# lcd-screen.net
KiCad netlist of a schematic drawn in EAGLE
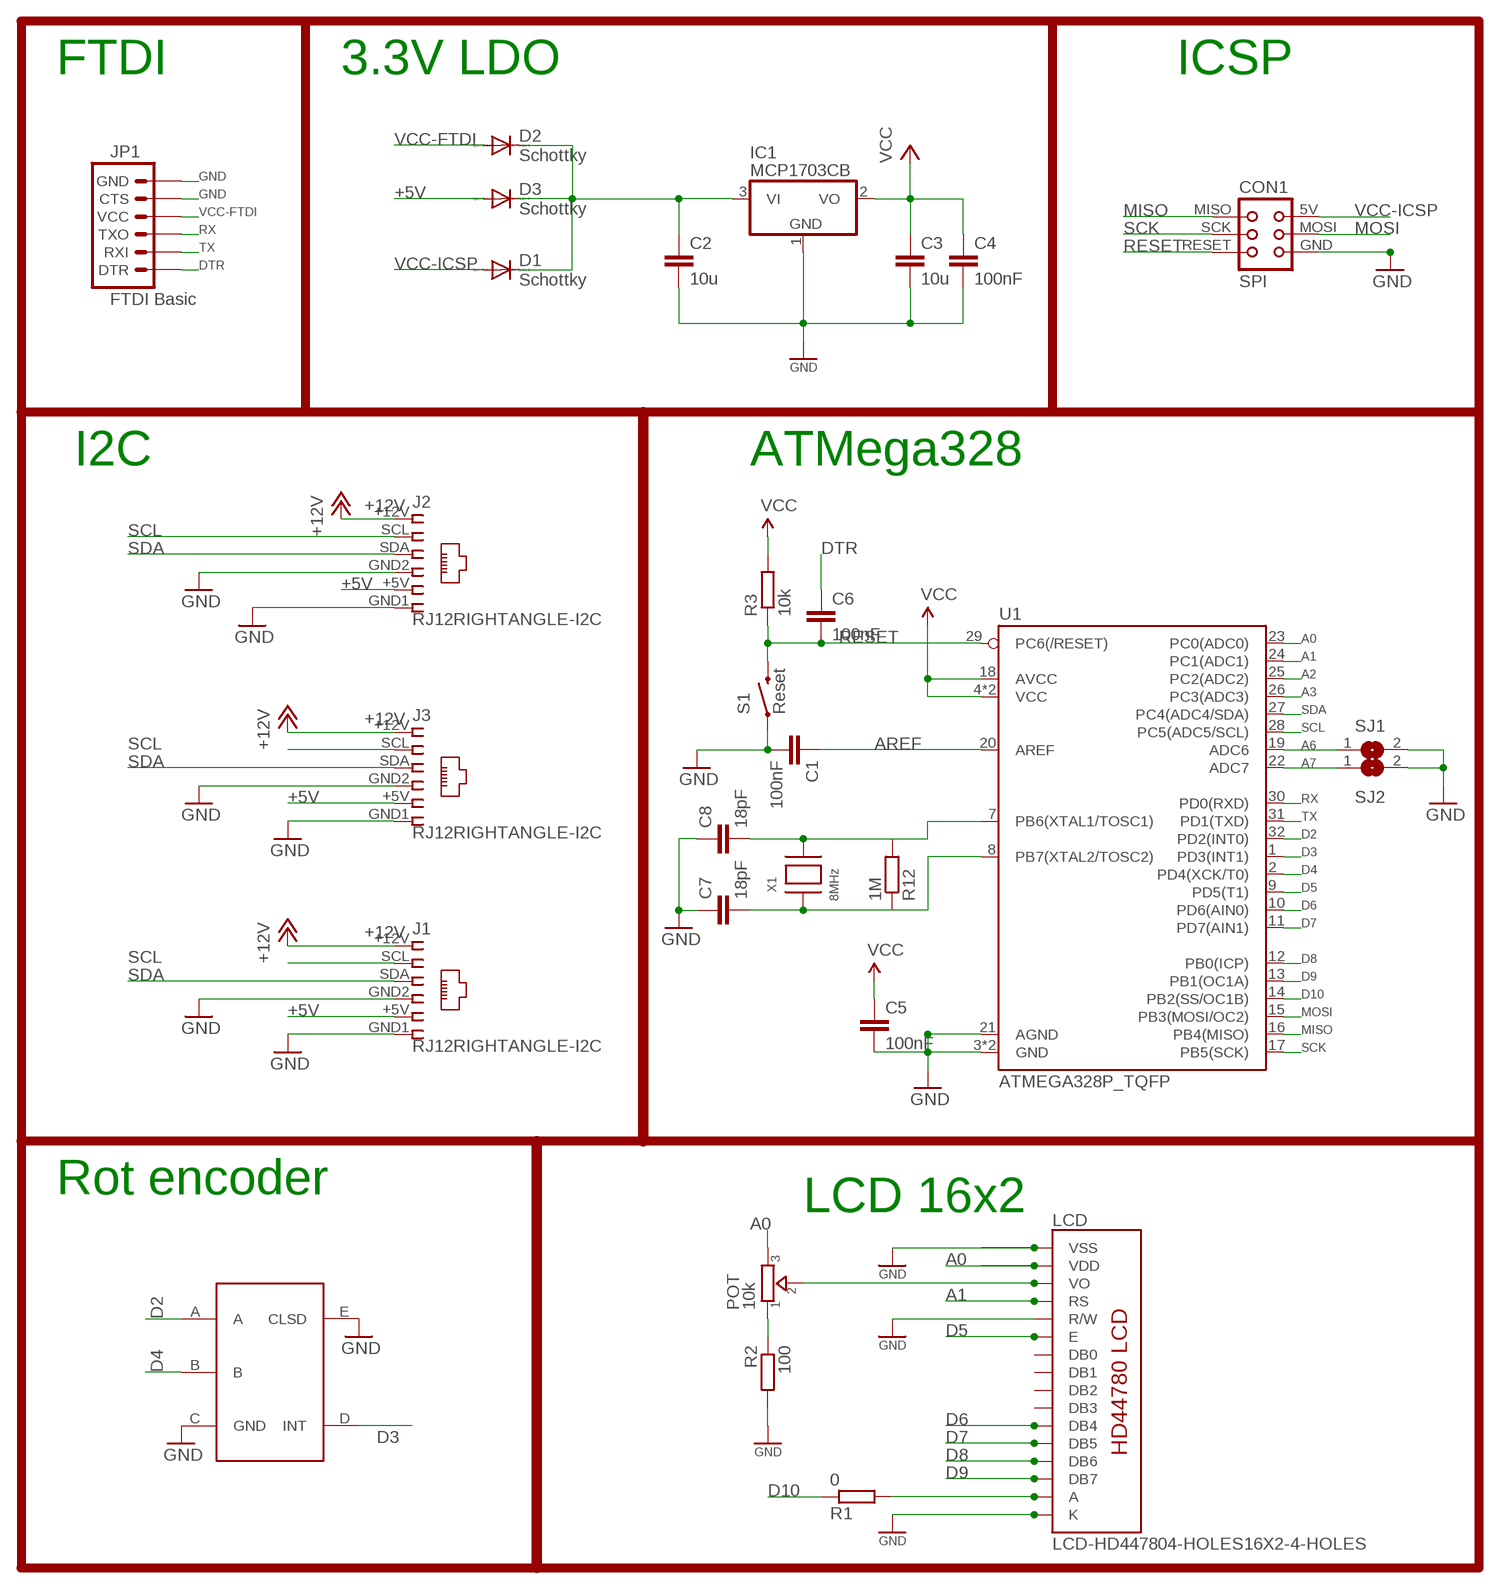
[diagram p0: schematic, sheet 1]

(export (version "E")
  (design (tool "Eeschema 10.0.6"))
  (components
    (comp (ref "C1")
      (value "100nF")
      (footprint "eagle-import:C0805K")
      (fields (field (name "MPN") "80-C1206C104K5R"))
      (libsource (lib "eagle-import") (part "C-EUC0805K"))
    )
    (comp (ref "C2")
      (value "10u")
      (footprint "eagle-import:C0805K")
      (fields (field (name "MPN") "77-VJ1206V106ZXQTBC"))
      (libsource (lib "eagle-import") (part "C-EUC0805K"))
    )
    (comp (ref "C3")
      (value "10u")
      (footprint "eagle-import:C0805K")
      (fields (field (name "MPN") "77-VJ1206V106ZXQTBC"))
      (libsource (lib "eagle-import") (part "C-EUC0805K"))
    )
    (comp (ref "C4")
      (value "100nF")
      (footprint "eagle-import:C0805K")
      (fields (field (name "MPN") "80-C1206C104K5R"))
      (libsource (lib "eagle-import") (part "C-EUC0805K"))
    )
    (comp (ref "C5")
      (value "100nF")
      (footprint "eagle-import:C0805K")
      (fields (field (name "MPN") "80-C1206C104K5R"))
      (libsource (lib "eagle-import") (part "C-EUC0805K"))
    )
    (comp (ref "C6")
      (value "100nF")
      (footprint "eagle-import:C0805K")
      (fields (field (name "MPN") "80-C1206C104K5R"))
      (libsource (lib "eagle-import") (part "C-EUC0805K"))
    )
    (comp (ref "C7")
      (value "18pF")
      (footprint "eagle-import:C0805K")
      (fields (field (name "MPN") "77-VJ1206A180JXXPBC"))
      (libsource (lib "eagle-import") (part "C-EUC0805K"))
    )
    (comp (ref "C8")
      (value "18pF")
      (footprint "eagle-import:C0805K")
      (fields (field (name "MPN") "77-VJ1206A180JXXPBC"))
      (libsource (lib "eagle-import") (part "C-EUC0805K"))
    )
    (comp (ref "CON1")
      (value "SPI")
      (footprint "eagle-import:TC2030-MCP")
      (libsource (lib "eagle-import") (part "TINYISPTAG"))
    )
    (comp (ref "D1")
      (value "Schottky")
      (footprint "eagle-import:SOD123")
      (fields (field (name "MPN") "621-1N5819HW-F"))
      (libsource (lib "eagle-import") (part "MBR0520LT"))
    )
    (comp (ref "D2")
      (value "Schottky")
      (footprint "eagle-import:SOD123")
      (fields (field (name "MPN") "621-1N5819HW-F"))
      (libsource (lib "eagle-import") (part "MBR0520LT"))
    )
    (comp (ref "D3")
      (value "Schottky")
      (footprint "eagle-import:SOD123")
      (fields (field (name "MPN") "621-1N5819HW-F"))
      (libsource (lib "eagle-import") (part "MBR0520LT"))
    )
    (comp (ref "IC1")
      (value "MCP1703CB")
      (footprint "eagle-import:SOT23")
      (libsource (lib "eagle-import") (part "MCP1703CB"))
    )
    (comp (ref "J1")
      (value "RJ12RIGHTANGLE-I2C")
      (footprint "eagle-import:RJ12-RIGHTANGLE-I2C")
      (libsource (lib "eagle-import") (part "RJ12RIGHTANGLE-I2C"))
    )
    (comp (ref "J2")
      (value "RJ12RIGHTANGLE-I2C")
      (footprint "eagle-import:RJ12-RIGHTANGLE-I2C")
      (libsource (lib "eagle-import") (part "RJ12RIGHTANGLE-I2C"))
    )
    (comp (ref "J3")
      (value "RJ12RIGHTANGLE-I2C")
      (footprint "eagle-import:RJ12-RIGHTANGLE-I2C")
      (libsource (lib "eagle-import") (part "RJ12RIGHTANGLE-I2C"))
    )
    (comp (ref "JP1")
      (value "FTDI Basic")
      (footprint "eagle-import:1X06")
      (libsource (lib "eagle-import") (part "ARDUINO_SERIAL_PROGRAMPTH"))
    )
    (comp (ref "LCD")
      (value "LCD-HD447804-HOLES16X2-4-HOLES")
      (footprint "eagle-import:LCD-16X2-4HOLES")
      (libsource (lib "eagle-import") (part "LCD-HD4478016X2-4-HOLES4-HOLES"))
    )
    (comp (ref "POT")
      (value "10k")
      (footprint "eagle-import:TRIMMER_3362P")
      (libsource (lib "eagle-import") (part "TRIMMER-3362P"))
    )
    (comp (ref "R1")
      (value "0")
      (footprint "eagle-import:R0805")
      (libsource (lib "eagle-import") (part "rcl_334_R-EU_R0805"))
    )
    (comp (ref "R2")
      (value "100")
      (footprint "eagle-import:R0805")
      (libsource (lib "eagle-import") (part "R-EU_R0805"))
    )
    (comp (ref "R3")
      (value "10k")
      (footprint "eagle-import:R0805")
      (libsource (lib "eagle-import") (part "R-EU_R0805"))
    )
    (comp (ref "R12")
      (value "1M")
      (footprint "eagle-import:R0805")
      (libsource (lib "eagle-import") (part "R-EU_R0805"))
    )
    (comp (ref "S1")
      (value "Reset")
      (footprint "eagle-import:TACTILE-SWITCH-SMD-ALT01")
      (libsource (lib "eagle-import") (part "SWITCH-MOMENTARY-2SMD-ALT01"))
    )
    (comp (ref "SJ1") (value "SJ") (footprint "eagle-import:SJ") (libsource (lib "eagle-import") (part "SJ")))
    (comp (ref "SJ2") (value "SJ") (footprint "eagle-import:SJ") (libsource (lib "eagle-import") (part "SJ")))
    (comp (ref "U$1")
      (value "EC11E")
      (footprint "eagle-import:EC11E")
      (libsource (lib "eagle-import") (part "EC11E"))
    )
    (comp (ref "U1")
      (value "ATMEGA328P_TQFP")
      (footprint "eagle-import:TQFP32-08")
      (libsource (lib "eagle-import") (part "ATMEGA328P_TQFP"))
    )
    (comp (ref "X1")
      (value "8MHz")
      (footprint "eagle-import:NX6035")
      (fields (field (name "MPN") "729-F60800010"))
      (libsource (lib "eagle-import") (part "XTALNX6035"))
    )
  )
  (nets
    (net (code "1") (name "+12V") (class "Default")
      (node (ref "J1") (pin "+12V") (pinfunction "1_+12V") (pintype "bidirectional"))
      (node (ref "J2") (pin "+12V") (pinfunction "1_+12V") (pintype "bidirectional"))
      (node (ref "J3") (pin "+12V") (pinfunction "1_+12V") (pintype "bidirectional"))
    )
    (net (code "2") (name "/+5V") (class "Default")
      (node (ref "D3") (pin "A") (pinfunction "A_A") (pintype "passive"))
      (node (ref "J1") (pin "+5V") (pinfunction "5_+5V") (pintype "bidirectional"))
      (node (ref "J2") (pin "+5V") (pinfunction "5_+5V") (pintype "bidirectional"))
      (node (ref "J3") (pin "+5V") (pinfunction "5_+5V") (pintype "bidirectional"))
    )
    (net (code "3") (name "/A0") (class "Default")
      (node (ref "LCD") (pin "2") (pinfunction "VDD_2") (pintype "power_in"))
      (node (ref "POT") (pin "3") (pinfunction "3_3") (pintype "passive"))
      (node (ref "U1") (pin "23") (pinfunction "PC0(ADC0)_23") (pintype "bidirectional"))
    )
    (net (code "4") (name "/A1") (class "Default")
      (node (ref "LCD") (pin "4") (pinfunction "RS_4") (pintype "input"))
      (node (ref "U1") (pin "24") (pinfunction "PC1(ADC1)_24") (pintype "bidirectional"))
    )
    (net (code "5") (name "/A2") (class "Default")
      (node (ref "U1") (pin "25") (pinfunction "PC2(ADC2)_25") (pintype "bidirectional"))
    )
    (net (code "6") (name "/A3") (class "Default")
      (node (ref "U1") (pin "26") (pinfunction "PC3(ADC3)_26") (pintype "bidirectional"))
    )
    (net (code "7") (name "/A6") (class "Default")
      (node (ref "SJ1") (pin "1") (pinfunction "1_1") (pintype "passive"))
      (node (ref "U1") (pin "19") (pinfunction "ADC6_19") (pintype "bidirectional"))
    )
    (net (code "8") (name "/A7") (class "Default")
      (node (ref "SJ2") (pin "1") (pinfunction "1_1") (pintype "passive"))
      (node (ref "U1") (pin "22") (pinfunction "ADC7_22") (pintype "bidirectional"))
    )
    (net (code "9") (name "/AREF") (class "Default")
      (node (ref "C1") (pin "1") (pinfunction "1_1") (pintype "passive"))
      (node (ref "U1") (pin "20") (pinfunction "AREF_20") (pintype "bidirectional"))
    )
    (net (code "10") (name "/D2") (class "Default")
      (node (ref "U$1") (pin "A") (pinfunction "A_A") (pintype "bidirectional"))
      (node (ref "U1") (pin "32") (pinfunction "PD2(INT0)_32") (pintype "bidirectional"))
    )
    (net (code "11") (name "/D3") (class "Default")
      (node (ref "U$1") (pin "D") (pinfunction "INT_D") (pintype "bidirectional"))
      (node (ref "U1") (pin "1") (pinfunction "PD3(INT1)_1") (pintype "bidirectional"))
    )
    (net (code "12") (name "/D4") (class "Default")
      (node (ref "U$1") (pin "B") (pinfunction "B_B") (pintype "bidirectional"))
      (node (ref "U1") (pin "2") (pinfunction "PD4(XCK/T0)_2") (pintype "bidirectional"))
    )
    (net (code "13") (name "/D5") (class "Default")
      (node (ref "LCD") (pin "6") (pinfunction "E_6") (pintype "input"))
      (node (ref "U1") (pin "9") (pinfunction "PD5(T1)_9") (pintype "bidirectional"))
    )
    (net (code "14") (name "/D6") (class "Default")
      (node (ref "LCD") (pin "11") (pinfunction "DB4_11") (pintype "bidirectional"))
      (node (ref "U1") (pin "10") (pinfunction "PD6(AIN0)_10") (pintype "bidirectional"))
    )
    (net (code "15") (name "/D7") (class "Default")
      (node (ref "LCD") (pin "12") (pinfunction "DB5_12") (pintype "bidirectional"))
      (node (ref "U1") (pin "11") (pinfunction "PD7(AIN1)_11") (pintype "bidirectional"))
    )
    (net (code "16") (name "/D8") (class "Default")
      (node (ref "LCD") (pin "13") (pinfunction "DB6_13") (pintype "bidirectional"))
      (node (ref "U1") (pin "12") (pinfunction "PB0(ICP)_12") (pintype "bidirectional"))
    )
    (net (code "17") (name "/D9") (class "Default")
      (node (ref "LCD") (pin "14") (pinfunction "DB7_14") (pintype "bidirectional"))
      (node (ref "U1") (pin "13") (pinfunction "PB1(OC1A)_13") (pintype "bidirectional"))
    )
    (net (code "18") (name "/D10") (class "Default")
      (node (ref "R1") (pin "1") (pinfunction "1_1") (pintype "passive"))
      (node (ref "U1") (pin "14") (pinfunction "PB2(SS/OC1B)_14") (pintype "bidirectional"))
    )
    (net (code "19") (name "/DTR") (class "Default")
      (node (ref "C6") (pin "1") (pinfunction "1_1") (pintype "passive"))
      (node (ref "JP1") (pin "1") (pinfunction "DTR_1") (pintype "passive"))
    )
    (net (code "20") (name "/MISO") (class "Default")
      (node (ref "CON1") (pin "MISO") (pinfunction "MISO_MISO") (pintype "passive"))
      (node (ref "U1") (pin "16") (pinfunction "PB4(MISO)_16") (pintype "bidirectional"))
    )
    (net (code "21") (name "/MOSI") (class "Default")
      (node (ref "CON1") (pin "MOSI") (pinfunction "MOSI_MOSI") (pintype "passive"))
      (node (ref "U1") (pin "15") (pinfunction "PB3(MOSI/OC2)_15") (pintype "bidirectional"))
    )
    (net (code "22") (name "/RESET") (class "Default")
      (node (ref "C6") (pin "2") (pinfunction "2_2") (pintype "passive"))
      (node (ref "CON1") (pin "RESET") (pinfunction "RESET_RESET") (pintype "passive"))
      (node (ref "R3") (pin "1") (pinfunction "1_1") (pintype "passive"))
      (node (ref "S1") (pin "3") (pinfunction "2_3") (pintype "passive"))
      (node (ref "S1") (pin "4") (pinfunction "2_4") (pintype "passive"))
      (node (ref "U1") (pin "29") (pinfunction "PC6(/RESET)_29") (pintype "bidirectional"))
    )
    (net (code "23") (name "/RX") (class "Default")
      (node (ref "JP1") (pin "3") (pinfunction "TXO_3") (pintype "passive"))
      (node (ref "U1") (pin "30") (pinfunction "PD0(RXD)_30") (pintype "bidirectional"))
    )
    (net (code "24") (name "/SCK") (class "Default")
      (node (ref "CON1") (pin "SCK") (pinfunction "SCK_SCK") (pintype "passive"))
      (node (ref "U1") (pin "17") (pinfunction "PB5(SCK)_17") (pintype "bidirectional"))
    )
    (net (code "25") (name "/SCL") (class "Default")
      (node (ref "J1") (pin "SCL") (pinfunction "2_SCL") (pintype "bidirectional"))
      (node (ref "J2") (pin "SCL") (pinfunction "2_SCL") (pintype "bidirectional"))
      (node (ref "J3") (pin "SCL") (pinfunction "2_SCL") (pintype "bidirectional"))
      (node (ref "U1") (pin "28") (pinfunction "PC5(ADC5/SCL)_28") (pintype "bidirectional"))
    )
    (net (code "26") (name "/SDA") (class "Default")
      (node (ref "J1") (pin "SDA") (pinfunction "3_SDA") (pintype "bidirectional"))
      (node (ref "J2") (pin "SDA") (pinfunction "3_SDA") (pintype "bidirectional"))
      (node (ref "J3") (pin "SDA") (pinfunction "3_SDA") (pintype "bidirectional"))
      (node (ref "U1") (pin "27") (pinfunction "PC4(ADC4/SDA)_27") (pintype "bidirectional"))
    )
    (net (code "27") (name "/TX") (class "Default")
      (node (ref "JP1") (pin "2") (pinfunction "RXI_2") (pintype "passive"))
      (node (ref "U1") (pin "31") (pinfunction "PD1(TXD)_31") (pintype "bidirectional"))
    )
    (net (code "28") (name "/VCC-FTDI") (class "Default")
      (node (ref "D2") (pin "A") (pinfunction "A_A") (pintype "passive"))
      (node (ref "JP1") (pin "4") (pinfunction "VCC_4") (pintype "passive"))
    )
    (net (code "29") (name "/VCC-ICSP") (class "Default")
      (node (ref "CON1") (pin "5V") (pinfunction "VCC_5V") (pintype "passive"))
      (node (ref "D1") (pin "A") (pinfunction "A_A") (pintype "passive"))
    )
    (net (code "30") (name "GND") (class "Default")
      (node (ref "C1") (pin "2") (pinfunction "2_2") (pintype "passive"))
      (node (ref "C2") (pin "2") (pinfunction "2_2") (pintype "passive"))
      (node (ref "C3") (pin "2") (pinfunction "2_2") (pintype "passive"))
      (node (ref "C4") (pin "2") (pinfunction "2_2") (pintype "passive"))
      (node (ref "C5") (pin "2") (pinfunction "2_2") (pintype "passive"))
      (node (ref "C7") (pin "1") (pinfunction "1_1") (pintype "passive"))
      (node (ref "C8") (pin "1") (pinfunction "1_1") (pintype "passive"))
      (node (ref "CON1") (pin "GND") (pinfunction "GND_GND") (pintype "passive"))
      (node (ref "IC1") (pin "1") (pinfunction "GND_1") (pintype "passive"))
      (node (ref "J1") (pin "GND1") (pinfunction "6_GND1") (pintype "bidirectional"))
      (node (ref "J1") (pin "GND2") (pinfunction "4_GND2") (pintype "bidirectional"))
      (node (ref "J2") (pin "GND1") (pinfunction "6_GND1") (pintype "bidirectional"))
      (node (ref "J2") (pin "GND2") (pinfunction "4_GND2") (pintype "bidirectional"))
      (node (ref "J3") (pin "GND1") (pinfunction "6_GND1") (pintype "bidirectional"))
      (node (ref "J3") (pin "GND2") (pinfunction "4_GND2") (pintype "bidirectional"))
      (node (ref "JP1") (pin "5") (pinfunction "CTS_5") (pintype "passive"))
      (node (ref "JP1") (pin "6") (pinfunction "GND_6") (pintype "passive"))
      (node (ref "LCD") (pin "1") (pinfunction "VSS_1") (pintype "power_in"))
      (node (ref "LCD") (pin "16") (pinfunction "K_16") (pintype "power_in"))
      (node (ref "LCD") (pin "5") (pinfunction "R/W_5") (pintype "input"))
      (node (ref "R2") (pin "2") (pinfunction "2_2") (pintype "passive"))
      (node (ref "S1") (pin "1") (pinfunction "1_1") (pintype "passive"))
      (node (ref "S1") (pin "2") (pinfunction "1_2") (pintype "passive"))
      (node (ref "SJ1") (pin "2") (pinfunction "2_2") (pintype "passive"))
      (node (ref "SJ2") (pin "2") (pinfunction "2_2") (pintype "passive"))
      (node (ref "U$1") (pin "C") (pinfunction "GND_C") (pintype "bidirectional"))
      (node (ref "U$1") (pin "E") (pinfunction "CLSD_E") (pintype "bidirectional"))
      (node (ref "U1") (pin "21") (pinfunction "AGND_21") (pintype "bidirectional"))
      (node (ref "U1") (pin "3") (pinfunction "GND_3") (pintype "bidirectional"))
      (node (ref "U1") (pin "5") (pinfunction "GND_5") (pintype "bidirectional"))
    )
    (net (code "31") (name "Net-(IC1-VI)") (class "Default")
      (node (ref "C2") (pin "1") (pinfunction "1_1") (pintype "passive"))
      (node (ref "D1") (pin "C") (pinfunction "C_C") (pintype "passive"))
      (node (ref "D2") (pin "C") (pinfunction "C_C") (pintype "passive"))
      (node (ref "D3") (pin "C") (pinfunction "C_C") (pintype "passive"))
      (node (ref "IC1") (pin "3") (pinfunction "VI_3") (pintype "input"))
    )
    (net (code "32") (name "Net-(LCD-A)") (class "Default")
      (node (ref "LCD") (pin "15") (pinfunction "A_15") (pintype "power_in"))
      (node (ref "R1") (pin "2") (pinfunction "2_2") (pintype "passive"))
    )
    (net (code "33") (name "Net-(LCD-VO)") (class "Default")
      (node (ref "LCD") (pin "3") (pinfunction "VO_3") (pintype "bidirectional"))
      (node (ref "POT") (pin "2") (pinfunction "2_2") (pintype "passive"))
    )
    (net (code "34") (name "Net-(POT-Pad1)") (class "Default")
      (node (ref "POT") (pin "1") (pinfunction "1_1") (pintype "passive"))
      (node (ref "R2") (pin "1") (pinfunction "1_1") (pintype "passive"))
    )
    (net (code "35") (name "Net-(U1-PB6(XTAL1{slash}TOSC1))") (class "Default")
      (node (ref "C8") (pin "2") (pinfunction "2_2") (pintype "passive"))
      (node (ref "R12") (pin "2") (pinfunction "2_2") (pintype "passive"))
      (node (ref "U1") (pin "7") (pinfunction "PB6(XTAL1/TOSC1)_7") (pintype "bidirectional"))
      (node (ref "X1") (pin "P$2") (pinfunction "P$2_P$2") (pintype "bidirectional"))
    )
    (net (code "36") (name "Net-(U1-PB7(XTAL2{slash}TOSC2))") (class "Default")
      (node (ref "C7") (pin "2") (pinfunction "2_2") (pintype "passive"))
      (node (ref "R12") (pin "1") (pinfunction "1_1") (pintype "passive"))
      (node (ref "U1") (pin "8") (pinfunction "PB7(XTAL2/TOSC2)_8") (pintype "bidirectional"))
      (node (ref "X1") (pin "P$1") (pinfunction "P$1_P$1") (pintype "bidirectional"))
    )
    (net (code "37") (name "VCC") (class "Default")
      (node (ref "C3") (pin "1") (pinfunction "1_1") (pintype "passive"))
      (node (ref "C4") (pin "1") (pinfunction "1_1") (pintype "passive"))
      (node (ref "C5") (pin "1") (pinfunction "1_1") (pintype "passive"))
      (node (ref "IC1") (pin "2") (pinfunction "VO_2") (pintype "passive"))
      (node (ref "R3") (pin "2") (pinfunction "2_2") (pintype "passive"))
      (node (ref "U1") (pin "18") (pinfunction "AVCC_18") (pintype "bidirectional"))
      (node (ref "U1") (pin "4") (pinfunction "VCC_4") (pintype "bidirectional"))
      (node (ref "U1") (pin "6") (pinfunction "VCC_6") (pintype "bidirectional"))
    )
    (net (code "38") (name "unconnected-(LCD-DB0-Pad7)") (class "Default")
      (node (ref "LCD") (pin "7") (pinfunction "DB0_7") (pintype "bidirectional"))
    )
    (net (code "39") (name "unconnected-(LCD-DB1-Pad8)") (class "Default")
      (node (ref "LCD") (pin "8") (pinfunction "DB1_8") (pintype "bidirectional"))
    )
    (net (code "40") (name "unconnected-(LCD-DB2-Pad9)") (class "Default")
      (node (ref "LCD") (pin "9") (pinfunction "DB2_9") (pintype "bidirectional"))
    )
    (net (code "41") (name "unconnected-(LCD-DB3-Pad10)") (class "Default")
      (node (ref "LCD") (pin "10") (pinfunction "DB3_10") (pintype "bidirectional"))
    )
  )
)
